# DC_MainBoard_Gh.net
KiCad netlist of a schematic drawn in EasyEDA Pro
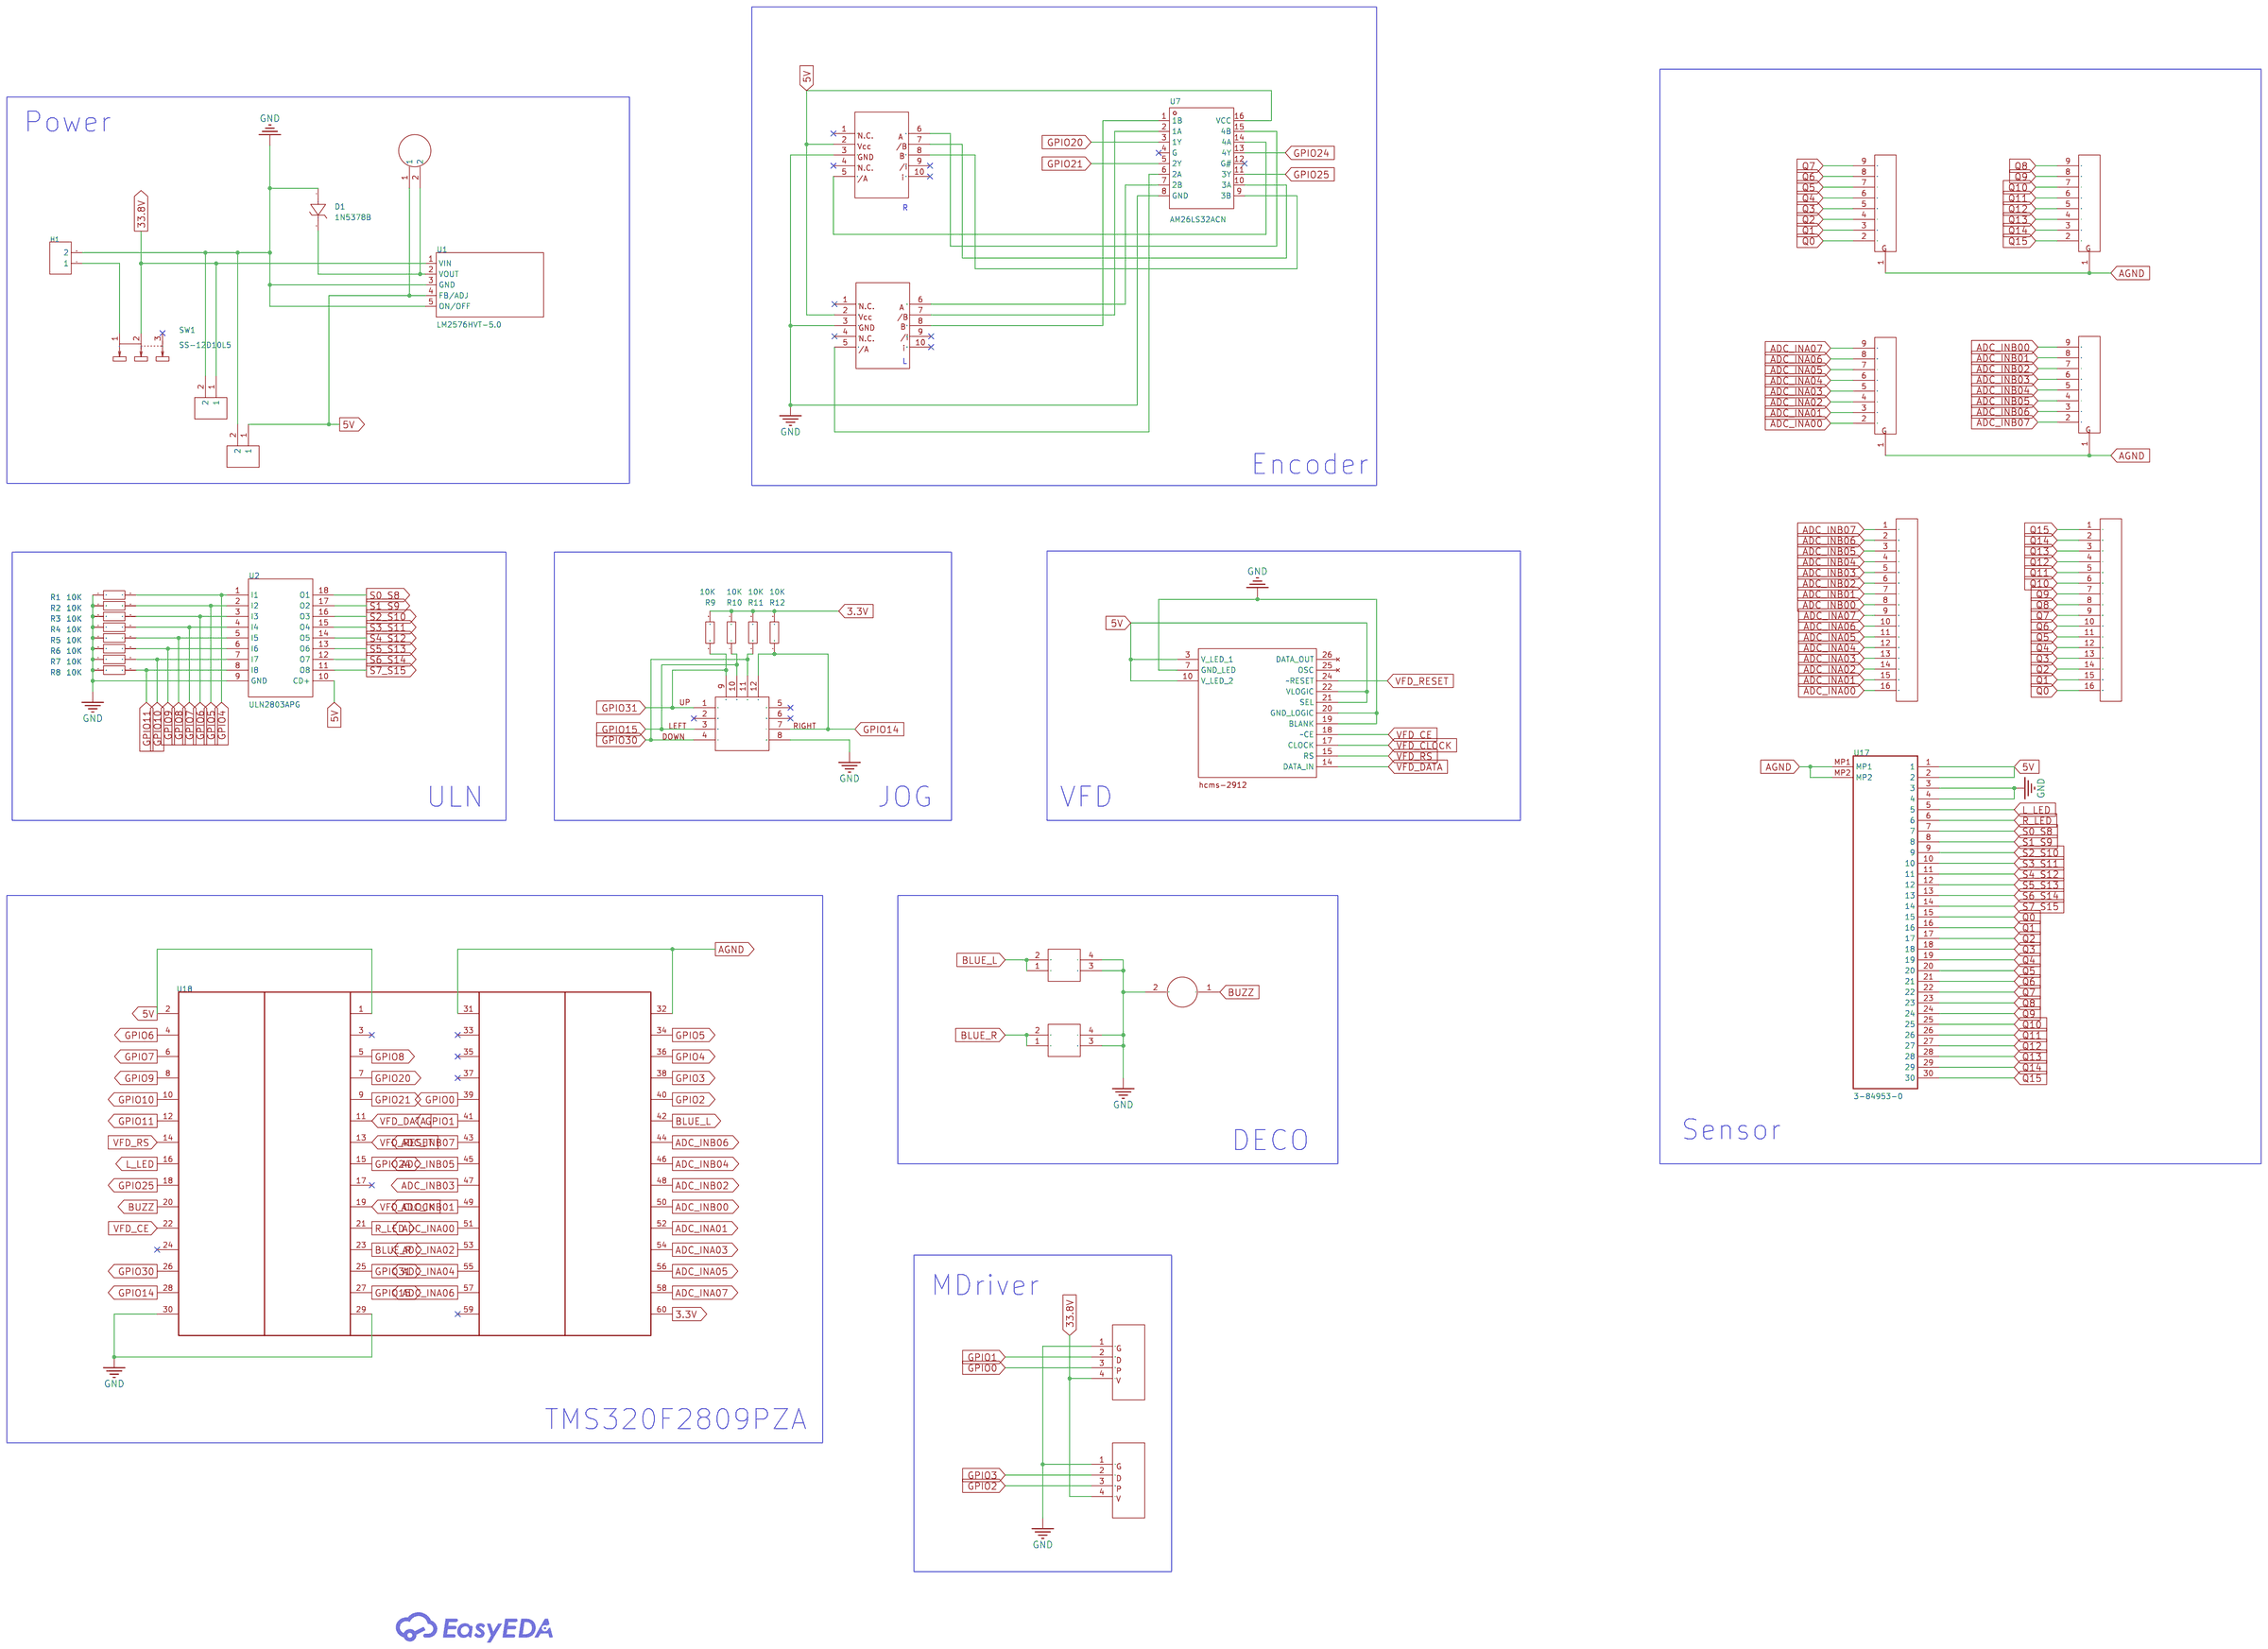
[diagram p0: schematic sheet]

(export (version "E")
  (design (tool "Eeschema 10.0.6"))
  (components
    (comp (ref "C1")
      (value "~")
      (footprint "easyedapro:100uF Capacitor")
      (libsource (lib "easyedapro") (part "100uF Capacitor"))
    )
    (comp (ref "C2")
      (value "~")
      (footprint "easyedapro:1000uF Capacitor")
      (libsource (lib "easyedapro") (part "1000uF Capacitor"))
    )
    (comp (ref "D1")
      (value "1N5378B")
      (footprint "easyedapro:DO-15_BD3.1-L6.7-P10.70-D0.9-FD")
      (fields (field (name "Manufacturer") "EIC"))
      (libsource (lib "easyedapro") (part "1N5378B"))
    )
    (comp (ref "H1")
      (value "~")
      (footprint "easyedapro:HDR-TH_2P-P2.54-V-F")
      (libsource (lib "easyedapro") (part "Header-Female-2.54_1x2"))
    )
    (comp (ref "L1")
      (value "~")
      (footprint "easyedapro:Indoctor")
      (libsource (lib "easyedapro") (part "Indoctor"))
    )
    (comp (ref "L2")
      (value "~")
      (footprint "easyedapro:NEMO_LED")
      (libsource (lib "easyedapro") (part "NEMO_LED"))
    )
    (comp (ref "L3")
      (value "~")
      (footprint "easyedapro:NEMO_LED")
      (libsource (lib "easyedapro") (part "NEMO_LED"))
    )
    (comp (ref "R1") (value "10K") (footprint "easyedapro:R0603") (libsource (lib "easyedapro") (part "Res")))
    (comp (ref "R2") (value "10K") (footprint "easyedapro:R0603") (libsource (lib "easyedapro") (part "Res")))
    (comp (ref "R3") (value "10K") (footprint "easyedapro:R0603") (libsource (lib "easyedapro") (part "Res")))
    (comp (ref "R4") (value "10K") (footprint "easyedapro:R0603") (libsource (lib "easyedapro") (part "Res")))
    (comp (ref "R5") (value "10K") (footprint "easyedapro:R0603") (libsource (lib "easyedapro") (part "Res")))
    (comp (ref "R6") (value "10K") (footprint "easyedapro:R0603") (libsource (lib "easyedapro") (part "Res")))
    (comp (ref "R7") (value "10K") (footprint "easyedapro:R0603") (libsource (lib "easyedapro") (part "Res")))
    (comp (ref "R8") (value "10K") (footprint "easyedapro:R0603") (libsource (lib "easyedapro") (part "Res")))
    (comp (ref "R9") (value "10K") (footprint "easyedapro:R0603") (libsource (lib "easyedapro") (part "Res")))
    (comp (ref "R10")
      (value "10K")
      (footprint "easyedapro:R0603")
      (libsource (lib "easyedapro") (part "Res"))
    )
    (comp (ref "R11")
      (value "10K")
      (footprint "easyedapro:R0603")
      (libsource (lib "easyedapro") (part "Res"))
    )
    (comp (ref "R12")
      (value "10K")
      (footprint "easyedapro:R0603")
      (libsource (lib "easyedapro") (part "Res"))
    )
    (comp (ref "SW1")
      (value "SS-12D10L5")
      (footprint "easyedapro:SW-TH_SS-12D10L5")
      (fields (field (name "Manufacturer") "XKB Connectivity(中国星坤)"))
      (libsource (lib "easyedapro") (part "SS-12D10L5"))
    )
    (comp (ref "U1")
      (value "LM2576HVT-5.0")
      (footprint "easyedapro:TO-220-5L_L10.2-W4.5-P1.71-L")
      (fields (field (name "Manufacturer") "HTC"))
      (libsource (lib "easyedapro") (part "LM2576HVT-5.0_C262789"))
    )
    (comp (ref "U2")
      (value "ULN2803APG")
      (footprint "easyedapro:DIP-18_L23.0-W6.5-P2.54-LS7.6-BL")
      (description "number of channels:Eight channels")
      (fields (field (name "Manufacturer") "TOSHIBA(东芝)"))
      (libsource (lib "easyedapro") (part "ULN2803APG"))
    )
    (comp (ref "U3")
      (value "~")
      (footprint "easyedapro:JOG_SW_DIP")
      (libsource (lib "easyedapro") (part "JOG_SW_DIP"))
    )
    (comp (ref "U4")
      (value "MDriver_L")
      (footprint "easyedapro:DC_Main_to_Motordriver_Connector_L")
      (libsource (lib "easyedapro") (part "DC_Main_to_Motordriver_Connector"))
    )
    (comp (ref "U5")
      (value "MDriver_R")
      (footprint "easyedapro:DC_Main_to_Motordriver_Connector_R")
      (libsource (lib "easyedapro") (part "DC_Main_to_Motordriver_Connector_R"))
    )
    (comp (ref "U6")
      (value "~")
      (footprint "easyedapro:BUZZER")
      (libsource (lib "easyedapro") (part "BUZZER"))
    )
    (comp (ref "U7")
      (value "AM26LS32ACN")
      (footprint "easyedapro:DIP-16_L20.0-W6.4-P2.54-LS7.6-BL")
      (fields (field (name "Manufacturer") "TI(德州仪器)"))
      (libsource (lib "easyedapro") (part "AM26LS32ACN"))
    )
    (comp (ref "U8")
      (value "~")
      (footprint "easyedapro:Encoder")
      (libsource (lib "easyedapro") (part "Encoder"))
    )
    (comp (ref "U9")
      (value "~")
      (footprint "easyedapro:Encoder")
      (libsource (lib "easyedapro") (part "Encoder"))
    )
    (comp (ref "U10") (value "~") (libsource (lib "easyedapro") (part "HCMS-2912")))
    (comp (ref "U11")
      (value "~")
      (footprint "easyedapro:Array")
      (libsource (lib "easyedapro") (part "Array"))
    )
    (comp (ref "U12")
      (value "~")
      (footprint "easyedapro:Array")
      (libsource (lib "easyedapro") (part "Array"))
    )
    (comp (ref "U13")
      (value "~")
      (footprint "easyedapro:Array")
      (libsource (lib "easyedapro") (part "Array"))
    )
    (comp (ref "U14")
      (value "~")
      (footprint "easyedapro:Array")
      (libsource (lib "easyedapro") (part "Array"))
    )
    (comp (ref "U15")
      (value "~")
      (footprint "easyedapro:C_Array")
      (libsource (lib "easyedapro") (part "C_Array"))
    )
    (comp (ref "U16")
      (value "~")
      (footprint "easyedapro:C_Array")
      (libsource (lib "easyedapro") (part "C_Array"))
    )
    (comp (ref "U17")
      (value "3-84953-0")
      (footprint "easyedapro:3849530")
      (libsource (lib "easyedapro") (part "3-84953-0"))
    )
    (comp (ref "U18") (value "~") (libsource (lib "easyedapro") (part "TMS320F2809PZA_DIP")))
  )
  (nets
    (net (code "1") (name "3.3V") (class "Default")
      (node (ref "R10") (pin "2") (pinfunction "2_2") (pintype "input"))
      (node (ref "R11") (pin "2") (pinfunction "2_2") (pintype "input"))
      (node (ref "R12") (pin "2") (pinfunction "2_2") (pintype "input"))
      (node (ref "R9") (pin "2") (pinfunction "2_2") (pintype "input"))
      (node (ref "U18") (pin "60") (pintype "unspecified"))
    )
    (net (code "2") (name "5V") (class "Default")
      (node (ref "C2") (pin "1") (pinfunction "1_1") (pintype "input"))
      (node (ref "L1") (pin "1") (pinfunction "1_1") (pintype "input"))
      (node (ref "U1") (pin "4") (pinfunction "FB/ADJ_4") (pintype "unspecified"))
      (node (ref "U10") (pin "10") (pinfunction "V_LED_2_10") (pintype "unspecified"))
      (node (ref "U10") (pin "21") (pinfunction "SEL_21") (pintype "unspecified"))
      (node (ref "U10") (pin "22") (pinfunction "VLOGIC_22") (pintype "unspecified"))
      (node (ref "U10") (pin "3") (pinfunction "V_LED_1_3") (pintype "unspecified"))
      (node (ref "U17") (pin "1") (pinfunction "1_1") (pintype "bidirectional"))
      (node (ref "U17") (pin "2") (pinfunction "2_2") (pintype "bidirectional"))
      (node (ref "U18") (pin "1") (pintype "unspecified"))
      (node (ref "U18") (pin "2") (pintype "unspecified"))
      (node (ref "U2") (pin "10") (pinfunction "CD+_10") (pintype "unspecified"))
      (node (ref "U7") (pin "16") (pinfunction "VCC_16") (pintype "unspecified"))
      (node (ref "U8") (pin "2") (pinfunction "2_2") (pintype "input"))
      (node (ref "U9") (pin "2") (pinfunction "2_2") (pintype "input"))
    )
    (net (code "3") (name "33.8V") (class "Default")
      (node (ref "C1") (pin "1") (pinfunction "1_1") (pintype "input"))
      (node (ref "SW1") (pin "2") (pinfunction "2_2") (pintype "unspecified"))
      (node (ref "U1") (pin "1") (pinfunction "VIN_1") (pintype "unspecified"))
      (node (ref "U4") (pin "4") (pinfunction "4_4") (pintype "input"))
      (node (ref "U5") (pin "4") (pinfunction "4_4") (pintype "input"))
    )
    (net (code "4") (name "ADC_INA00") (class "Default")
      (node (ref "U13") (pin "2") (pinfunction "2_2") (pintype "input"))
      (node (ref "U15") (pin "16") (pinfunction "16_16") (pintype "input"))
      (node (ref "U18") (pin "51") (pintype "unspecified"))
    )
    (net (code "5") (name "ADC_INA01") (class "Default")
      (node (ref "U13") (pin "3") (pinfunction "3_3") (pintype "input"))
      (node (ref "U15") (pin "15") (pinfunction "15_15") (pintype "input"))
      (node (ref "U18") (pin "52") (pintype "unspecified"))
    )
    (net (code "6") (name "ADC_INA02") (class "Default")
      (node (ref "U13") (pin "4") (pinfunction "4_4") (pintype "input"))
      (node (ref "U15") (pin "14") (pinfunction "14_14") (pintype "input"))
      (node (ref "U18") (pin "53") (pintype "unspecified"))
    )
    (net (code "7") (name "ADC_INA03") (class "Default")
      (node (ref "U13") (pin "5") (pinfunction "5_5") (pintype "input"))
      (node (ref "U15") (pin "13") (pinfunction "13_13") (pintype "input"))
      (node (ref "U18") (pin "54") (pintype "unspecified"))
    )
    (net (code "8") (name "ADC_INA04") (class "Default")
      (node (ref "U13") (pin "6") (pinfunction "6_6") (pintype "input"))
      (node (ref "U15") (pin "12") (pinfunction "12_12") (pintype "input"))
      (node (ref "U18") (pin "55") (pintype "unspecified"))
    )
    (net (code "9") (name "ADC_INA05") (class "Default")
      (node (ref "U13") (pin "7") (pinfunction "7_7") (pintype "input"))
      (node (ref "U15") (pin "11") (pinfunction "11_11") (pintype "input"))
      (node (ref "U18") (pin "56") (pintype "unspecified"))
    )
    (net (code "10") (name "ADC_INA06") (class "Default")
      (node (ref "U13") (pin "8") (pinfunction "8_8") (pintype "input"))
      (node (ref "U15") (pin "10") (pinfunction "10_10") (pintype "input"))
      (node (ref "U18") (pin "57") (pintype "unspecified"))
    )
    (net (code "11") (name "ADC_INA07") (class "Default")
      (node (ref "U13") (pin "9") (pinfunction "9_9") (pintype "input"))
      (node (ref "U15") (pin "9") (pinfunction "9_9") (pintype "input"))
      (node (ref "U18") (pin "58") (pintype "unspecified"))
    )
    (net (code "12") (name "ADC_INB00") (class "Default")
      (node (ref "U14") (pin "9") (pinfunction "9_9") (pintype "input"))
      (node (ref "U15") (pin "8") (pinfunction "8_8") (pintype "input"))
      (node (ref "U18") (pin "50") (pintype "unspecified"))
    )
    (net (code "13") (name "ADC_INB01") (class "Default")
      (node (ref "U14") (pin "8") (pinfunction "8_8") (pintype "input"))
      (node (ref "U15") (pin "7") (pinfunction "7_7") (pintype "input"))
      (node (ref "U18") (pin "49") (pintype "unspecified"))
    )
    (net (code "14") (name "ADC_INB02") (class "Default")
      (node (ref "U14") (pin "7") (pinfunction "7_7") (pintype "input"))
      (node (ref "U15") (pin "6") (pinfunction "6_6") (pintype "input"))
      (node (ref "U18") (pin "48") (pintype "unspecified"))
    )
    (net (code "15") (name "ADC_INB03") (class "Default")
      (node (ref "U14") (pin "6") (pinfunction "6_6") (pintype "input"))
      (node (ref "U15") (pin "5") (pinfunction "5_5") (pintype "input"))
      (node (ref "U18") (pin "47") (pintype "unspecified"))
    )
    (net (code "16") (name "ADC_INB04") (class "Default")
      (node (ref "U14") (pin "5") (pinfunction "5_5") (pintype "input"))
      (node (ref "U15") (pin "4") (pinfunction "4_4") (pintype "input"))
      (node (ref "U18") (pin "46") (pintype "unspecified"))
    )
    (net (code "17") (name "ADC_INB05") (class "Default")
      (node (ref "U14") (pin "4") (pinfunction "4_4") (pintype "input"))
      (node (ref "U15") (pin "3") (pinfunction "3_3") (pintype "input"))
      (node (ref "U18") (pin "45") (pintype "unspecified"))
    )
    (net (code "18") (name "ADC_INB06") (class "Default")
      (node (ref "U14") (pin "3") (pinfunction "3_3") (pintype "input"))
      (node (ref "U15") (pin "2") (pinfunction "2_2") (pintype "input"))
      (node (ref "U18") (pin "44") (pintype "unspecified"))
    )
    (net (code "19") (name "ADC_INB07") (class "Default")
      (node (ref "U14") (pin "2") (pinfunction "2_2") (pintype "input"))
      (node (ref "U15") (pin "1") (pinfunction "1_1") (pintype "input"))
      (node (ref "U18") (pin "43") (pintype "unspecified"))
    )
    (net (code "20") (name "AGND") (class "Default")
      (node (ref "U11") (pin "1") (pinfunction "1_1") (pintype "input"))
      (node (ref "U12") (pin "1") (pinfunction "1_1") (pintype "input"))
      (node (ref "U13") (pin "1") (pinfunction "1_1") (pintype "input"))
      (node (ref "U14") (pin "1") (pinfunction "1_1") (pintype "input"))
      (node (ref "U17") (pin "MP1") (pinfunction "MP1_MP1") (pintype "bidirectional"))
      (node (ref "U17") (pin "MP2") (pinfunction "MP2_MP2") (pintype "bidirectional"))
      (node (ref "U18") (pin "31") (pintype "unspecified"))
      (node (ref "U18") (pin "32") (pintype "unspecified"))
    )
    (net (code "21") (name "BLUE_L") (class "Default")
      (node (ref "L2") (pin "1") (pinfunction "1_1") (pintype "input"))
      (node (ref "L2") (pin "2") (pinfunction "2_2") (pintype "input"))
      (node (ref "U18") (pin "42") (pintype "unspecified"))
    )
    (net (code "22") (name "BLUE_R") (class "Default")
      (node (ref "L3") (pin "1") (pinfunction "1_1") (pintype "input"))
      (node (ref "L3") (pin "2") (pinfunction "2_2") (pintype "input"))
      (node (ref "U18") (pin "23") (pintype "unspecified"))
    )
    (net (code "23") (name "BUZZ") (class "Default")
      (node (ref "U18") (pin "20") (pintype "unspecified"))
      (node (ref "U6") (pin "1") (pinfunction "1_1") (pintype "input"))
    )
    (net (code "24") (name "GND") (class "Default")
      (node (ref "C1") (pin "2") (pinfunction "2_2") (pintype "input"))
      (node (ref "C2") (pin "2") (pinfunction "2_2") (pintype "input"))
      (node (ref "D1") (pin "1") (pinfunction "+_1") (pintype "unspecified"))
      (node (ref "H1") (pin "2") (pinfunction "2_2") (pintype "input"))
      (node (ref "L2") (pin "3") (pinfunction "3_3") (pintype "input"))
      (node (ref "L2") (pin "4") (pinfunction "4_4") (pintype "input"))
      (node (ref "L3") (pin "3") (pinfunction "3_3") (pintype "input"))
      (node (ref "L3") (pin "4") (pinfunction "4_4") (pintype "input"))
      (node (ref "R1") (pin "1") (pinfunction "1_1") (pintype "input"))
      (node (ref "R2") (pin "1") (pinfunction "1_1") (pintype "input"))
      (node (ref "R3") (pin "1") (pinfunction "1_1") (pintype "input"))
      (node (ref "R4") (pin "1") (pinfunction "1_1") (pintype "input"))
      (node (ref "R5") (pin "1") (pinfunction "1_1") (pintype "input"))
      (node (ref "R6") (pin "1") (pinfunction "1_1") (pintype "input"))
      (node (ref "R7") (pin "1") (pinfunction "1_1") (pintype "input"))
      (node (ref "R8") (pin "1") (pinfunction "1_1") (pintype "input"))
      (node (ref "U1") (pin "3") (pinfunction "GND_3") (pintype "unspecified"))
      (node (ref "U1") (pin "5") (pinfunction "ON/OFF_5") (pintype "unspecified"))
      (node (ref "U10") (pin "19") (pinfunction "BLANK_19") (pintype "unspecified"))
      (node (ref "U10") (pin "20") (pinfunction "GND_LOGIC_20") (pintype "unspecified"))
      (node (ref "U10") (pin "7") (pinfunction "GND_LED_7") (pintype "unspecified"))
      (node (ref "U17") (pin "3") (pinfunction "3_3") (pintype "bidirectional"))
      (node (ref "U17") (pin "4") (pinfunction "4_4") (pintype "bidirectional"))
      (node (ref "U18") (pin "29") (pintype "unspecified"))
      (node (ref "U18") (pin "30") (pintype "unspecified"))
      (node (ref "U2") (pin "9") (pinfunction "GND_9") (pintype "unspecified"))
      (node (ref "U3") (pin "8") (pinfunction "8_8") (pintype "input"))
      (node (ref "U4") (pin "1") (pinfunction "1_1") (pintype "input"))
      (node (ref "U5") (pin "1") (pinfunction "1_1") (pintype "input"))
      (node (ref "U6") (pin "2") (pinfunction "2_2") (pintype "input"))
      (node (ref "U7") (pin "8") (pinfunction "GND_8") (pintype "unspecified"))
      (node (ref "U8") (pin "3") (pinfunction "3_3") (pintype "input"))
      (node (ref "U9") (pin "3") (pinfunction "3_3") (pintype "input"))
    )
    (net (code "25") (name "GPIO0") (class "Default")
      (node (ref "U18") (pin "39") (pintype "unspecified"))
      (node (ref "U4") (pin "3") (pinfunction "3_3") (pintype "input"))
    )
    (net (code "26") (name "GPIO1") (class "Default")
      (node (ref "U18") (pin "41") (pintype "unspecified"))
      (node (ref "U4") (pin "2") (pinfunction "2_2") (pintype "input"))
    )
    (net (code "27") (name "GPIO2") (class "Default")
      (node (ref "U18") (pin "40") (pintype "unspecified"))
      (node (ref "U5") (pin "3") (pinfunction "3_3") (pintype "input"))
    )
    (net (code "28") (name "GPIO3") (class "Default")
      (node (ref "U18") (pin "38") (pintype "unspecified"))
      (node (ref "U5") (pin "2") (pinfunction "2_2") (pintype "input"))
    )
    (net (code "29") (name "GPIO4") (class "Default")
      (node (ref "R1") (pin "2") (pinfunction "2_2") (pintype "input"))
      (node (ref "U18") (pin "36") (pintype "unspecified"))
      (node (ref "U2") (pin "1") (pinfunction "I1_1") (pintype "input"))
    )
    (net (code "30") (name "GPIO5") (class "Default")
      (node (ref "R2") (pin "2") (pinfunction "2_2") (pintype "input"))
      (node (ref "U18") (pin "34") (pintype "unspecified"))
      (node (ref "U2") (pin "2") (pinfunction "I2_2") (pintype "input"))
    )
    (net (code "31") (name "GPIO6") (class "Default")
      (node (ref "R3") (pin "2") (pinfunction "2_2") (pintype "input"))
      (node (ref "U18") (pin "4") (pintype "unspecified"))
      (node (ref "U2") (pin "3") (pinfunction "I3_3") (pintype "input"))
    )
    (net (code "32") (name "GPIO7") (class "Default")
      (node (ref "R4") (pin "2") (pinfunction "2_2") (pintype "input"))
      (node (ref "U18") (pin "6") (pintype "unspecified"))
      (node (ref "U2") (pin "4") (pinfunction "I4_4") (pintype "input"))
    )
    (net (code "33") (name "GPIO8") (class "Default")
      (node (ref "R5") (pin "2") (pinfunction "2_2") (pintype "input"))
      (node (ref "U18") (pin "5") (pintype "unspecified"))
      (node (ref "U2") (pin "5") (pinfunction "I5_5") (pintype "input"))
    )
    (net (code "34") (name "GPIO9") (class "Default")
      (node (ref "R6") (pin "2") (pinfunction "2_2") (pintype "input"))
      (node (ref "U18") (pin "8") (pintype "unspecified"))
      (node (ref "U2") (pin "6") (pinfunction "I6_6") (pintype "input"))
    )
    (net (code "35") (name "GPIO10") (class "Default")
      (node (ref "R7") (pin "2") (pinfunction "2_2") (pintype "input"))
      (node (ref "U18") (pin "10") (pintype "unspecified"))
      (node (ref "U2") (pin "7") (pinfunction "I7_7") (pintype "input"))
    )
    (net (code "36") (name "GPIO11") (class "Default")
      (node (ref "R8") (pin "2") (pinfunction "2_2") (pintype "input"))
      (node (ref "U18") (pin "12") (pintype "unspecified"))
      (node (ref "U2") (pin "8") (pinfunction "I8_8") (pintype "input"))
    )
    (net (code "37") (name "GPIO14") (class "Default")
      (node (ref "R12") (pin "1") (pinfunction "1_1") (pintype "input"))
      (node (ref "U18") (pin "28") (pintype "unspecified"))
      (node (ref "U3") (pin "12") (pinfunction "12_12") (pintype "input"))
      (node (ref "U3") (pin "7") (pinfunction "7_7") (pintype "input"))
    )
    (net (code "38") (name "GPIO15") (class "Default")
      (node (ref "R10") (pin "1") (pinfunction "1_1") (pintype "input"))
      (node (ref "U18") (pin "27") (pintype "unspecified"))
      (node (ref "U3") (pin "10") (pinfunction "10_10") (pintype "input"))
      (node (ref "U3") (pin "3") (pinfunction "3_3") (pintype "input"))
    )
    (net (code "39") (name "GPIO20") (class "Default")
      (node (ref "U18") (pin "7") (pintype "unspecified"))
      (node (ref "U7") (pin "3") (pinfunction "1Y_3") (pintype "unspecified"))
    )
    (net (code "40") (name "GPIO21") (class "Default")
      (node (ref "U18") (pin "9") (pintype "unspecified"))
      (node (ref "U7") (pin "5") (pinfunction "2Y_5") (pintype "unspecified"))
    )
    (net (code "41") (name "GPIO24") (class "Default")
      (node (ref "U18") (pin "15") (pintype "unspecified"))
      (node (ref "U7") (pin "13") (pinfunction "4Y_13") (pintype "unspecified"))
    )
    (net (code "42") (name "GPIO25") (class "Default")
      (node (ref "U18") (pin "18") (pintype "unspecified"))
      (node (ref "U7") (pin "11") (pinfunction "3Y_11") (pintype "unspecified"))
    )
    (net (code "43") (name "GPIO30") (class "Default")
      (node (ref "R11") (pin "1") (pinfunction "1_1") (pintype "input"))
      (node (ref "U18") (pin "26") (pintype "unspecified"))
      (node (ref "U3") (pin "11") (pinfunction "11_11") (pintype "input"))
      (node (ref "U3") (pin "4") (pinfunction "4_4") (pintype "input"))
    )
    (net (code "44") (name "GPIO31") (class "Default")
      (node (ref "R9") (pin "1") (pinfunction "1_1") (pintype "input"))
      (node (ref "U18") (pin "25") (pintype "unspecified"))
      (node (ref "U3") (pin "1") (pinfunction "1_1") (pintype "input"))
      (node (ref "U3") (pin "9") (pinfunction "9_9") (pintype "input"))
    )
    (net (code "45") (name "L_LED") (class "Default")
      (node (ref "U17") (pin "5") (pinfunction "5_5") (pintype "bidirectional"))
      (node (ref "U18") (pin "16") (pintype "unspecified"))
    )
    (net (code "46") (name "Net-(D1--)") (class "Default")
      (node (ref "D1") (pin "2") (pinfunction "-_2") (pintype "unspecified"))
      (node (ref "L1") (pin "2") (pinfunction "2_2") (pintype "input"))
      (node (ref "U1") (pin "2") (pinfunction "VOUT_2") (pintype "unspecified"))
    )
    (net (code "47") (name "Net-(H1-Pad1)") (class "Default")
      (node (ref "H1") (pin "1") (pinfunction "1_1") (pintype "input"))
      (node (ref "SW1") (pin "1") (pinfunction "1_1") (pintype "unspecified"))
    )
    (net (code "48") (name "Net-(U7-1A)") (class "Default")
      (node (ref "U7") (pin "2") (pinfunction "1A_2") (pintype "unspecified"))
      (node (ref "U8") (pin "7") (pinfunction "7_7") (pintype "input"))
    )
    (net (code "49") (name "Net-(U7-1B)") (class "Default")
      (node (ref "U7") (pin "1") (pinfunction "1B_1") (pintype "unspecified"))
      (node (ref "U8") (pin "8") (pinfunction "8_8") (pintype "input"))
    )
    (net (code "50") (name "Net-(U7-2A)") (class "Default")
      (node (ref "U7") (pin "6") (pinfunction "2A_6") (pintype "unspecified"))
      (node (ref "U8") (pin "5") (pinfunction "5_5") (pintype "input"))
    )
    (net (code "51") (name "Net-(U7-2B)") (class "Default")
      (node (ref "U7") (pin "7") (pinfunction "2B_7") (pintype "unspecified"))
      (node (ref "U8") (pin "6") (pinfunction "6_6") (pintype "input"))
    )
    (net (code "52") (name "Net-(U7-3A)") (class "Default")
      (node (ref "U7") (pin "10") (pinfunction "3A_10") (pintype "unspecified"))
      (node (ref "U9") (pin "7") (pinfunction "7_7") (pintype "input"))
    )
    (net (code "53") (name "Net-(U7-3B)") (class "Default")
      (node (ref "U7") (pin "9") (pinfunction "3B_9") (pintype "unspecified"))
      (node (ref "U9") (pin "8") (pinfunction "8_8") (pintype "input"))
    )
    (net (code "54") (name "Net-(U7-4A)") (class "Default")
      (node (ref "U7") (pin "14") (pinfunction "4A_14") (pintype "unspecified"))
      (node (ref "U9") (pin "5") (pinfunction "5_5") (pintype "input"))
    )
    (net (code "55") (name "Net-(U7-4B)") (class "Default")
      (node (ref "U7") (pin "15") (pinfunction "4B_15") (pintype "unspecified"))
      (node (ref "U9") (pin "6") (pinfunction "6_6") (pintype "input"))
    )
    (net (code "56") (name "Q0") (class "Default")
      (node (ref "U11") (pin "2") (pinfunction "2_2") (pintype "input"))
      (node (ref "U16") (pin "16") (pinfunction "16_16") (pintype "input"))
      (node (ref "U17") (pin "15") (pinfunction "15_15") (pintype "bidirectional"))
    )
    (net (code "57") (name "Q1") (class "Default")
      (node (ref "U11") (pin "3") (pinfunction "3_3") (pintype "input"))
      (node (ref "U16") (pin "15") (pinfunction "15_15") (pintype "input"))
      (node (ref "U17") (pin "16") (pinfunction "16_16") (pintype "bidirectional"))
    )
    (net (code "58") (name "Q2") (class "Default")
      (node (ref "U11") (pin "4") (pinfunction "4_4") (pintype "input"))
      (node (ref "U16") (pin "14") (pinfunction "14_14") (pintype "input"))
      (node (ref "U17") (pin "17") (pinfunction "17_17") (pintype "bidirectional"))
    )
    (net (code "59") (name "Q3") (class "Default")
      (node (ref "U11") (pin "5") (pinfunction "5_5") (pintype "input"))
      (node (ref "U16") (pin "13") (pinfunction "13_13") (pintype "input"))
      (node (ref "U17") (pin "18") (pinfunction "18_18") (pintype "bidirectional"))
    )
    (net (code "60") (name "Q4") (class "Default")
      (node (ref "U11") (pin "6") (pinfunction "6_6") (pintype "input"))
      (node (ref "U16") (pin "12") (pinfunction "12_12") (pintype "input"))
      (node (ref "U17") (pin "19") (pinfunction "19_19") (pintype "bidirectional"))
    )
    (net (code "61") (name "Q5") (class "Default")
      (node (ref "U11") (pin "7") (pinfunction "7_7") (pintype "input"))
      (node (ref "U16") (pin "11") (pinfunction "11_11") (pintype "input"))
      (node (ref "U17") (pin "20") (pinfunction "20_20") (pintype "bidirectional"))
    )
    (net (code "62") (name "Q6") (class "Default")
      (node (ref "U11") (pin "8") (pinfunction "8_8") (pintype "input"))
      (node (ref "U16") (pin "10") (pinfunction "10_10") (pintype "input"))
      (node (ref "U17") (pin "21") (pinfunction "21_21") (pintype "bidirectional"))
    )
    (net (code "63") (name "Q7") (class "Default")
      (node (ref "U11") (pin "9") (pinfunction "9_9") (pintype "input"))
      (node (ref "U16") (pin "9") (pinfunction "9_9") (pintype "input"))
      (node (ref "U17") (pin "22") (pinfunction "22_22") (pintype "bidirectional"))
    )
    (net (code "64") (name "Q8") (class "Default")
      (node (ref "U12") (pin "9") (pinfunction "9_9") (pintype "input"))
      (node (ref "U16") (pin "8") (pinfunction "8_8") (pintype "input"))
      (node (ref "U17") (pin "23") (pinfunction "23_23") (pintype "bidirectional"))
    )
    (net (code "65") (name "Q9") (class "Default")
      (node (ref "U12") (pin "8") (pinfunction "8_8") (pintype "input"))
      (node (ref "U16") (pin "7") (pinfunction "7_7") (pintype "input"))
      (node (ref "U17") (pin "24") (pinfunction "24_24") (pintype "bidirectional"))
    )
    (net (code "66") (name "Q10") (class "Default")
      (node (ref "U12") (pin "7") (pinfunction "7_7") (pintype "input"))
      (node (ref "U16") (pin "6") (pinfunction "6_6") (pintype "input"))
      (node (ref "U17") (pin "25") (pinfunction "25_25") (pintype "bidirectional"))
    )
    (net (code "67") (name "Q11") (class "Default")
      (node (ref "U12") (pin "6") (pinfunction "6_6") (pintype "input"))
      (node (ref "U16") (pin "5") (pinfunction "5_5") (pintype "input"))
      (node (ref "U17") (pin "26") (pinfunction "26_26") (pintype "bidirectional"))
    )
    (net (code "68") (name "Q12") (class "Default")
      (node (ref "U12") (pin "5") (pinfunction "5_5") (pintype "input"))
      (node (ref "U16") (pin "4") (pinfunction "4_4") (pintype "input"))
      (node (ref "U17") (pin "27") (pinfunction "27_27") (pintype "bidirectional"))
    )
    (net (code "69") (name "Q13") (class "Default")
      (node (ref "U12") (pin "4") (pinfunction "4_4") (pintype "input"))
      (node (ref "U16") (pin "3") (pinfunction "3_3") (pintype "input"))
      (node (ref "U17") (pin "28") (pinfunction "28_28") (pintype "bidirectional"))
    )
    (net (code "70") (name "Q14") (class "Default")
      (node (ref "U12") (pin "3") (pinfunction "3_3") (pintype "input"))
      (node (ref "U16") (pin "2") (pinfunction "2_2") (pintype "input"))
      (node (ref "U17") (pin "29") (pinfunction "29_29") (pintype "bidirectional"))
    )
    (net (code "71") (name "Q15") (class "Default")
      (node (ref "U12") (pin "2") (pinfunction "2_2") (pintype "input"))
      (node (ref "U16") (pin "1") (pinfunction "1_1") (pintype "input"))
      (node (ref "U17") (pin "30") (pinfunction "30_30") (pintype "bidirectional"))
    )
    (net (code "72") (name "R_LED") (class "Default")
      (node (ref "U17") (pin "6") (pinfunction "6_6") (pintype "bidirectional"))
      (node (ref "U18") (pin "21") (pintype "unspecified"))
    )
    (net (code "73") (name "S0_S8") (class "Default")
      (node (ref "U17") (pin "7") (pinfunction "7_7") (pintype "bidirectional"))
      (node (ref "U2") (pin "18") (pinfunction "O1_18") (pintype "unspecified"))
    )
    (net (code "74") (name "S1_S9") (class "Default")
      (node (ref "U17") (pin "8") (pinfunction "8_8") (pintype "bidirectional"))
      (node (ref "U2") (pin "17") (pinfunction "O2_17") (pintype "unspecified"))
    )
    (net (code "75") (name "S2_S10") (class "Default")
      (node (ref "U17") (pin "9") (pinfunction "9_9") (pintype "bidirectional"))
      (node (ref "U2") (pin "16") (pinfunction "O3_16") (pintype "unspecified"))
    )
    (net (code "76") (name "S3_S11") (class "Default")
      (node (ref "U17") (pin "10") (pinfunction "10_10") (pintype "bidirectional"))
      (node (ref "U2") (pin "15") (pinfunction "O4_15") (pintype "unspecified"))
    )
    (net (code "77") (name "S4_S12") (class "Default")
      (node (ref "U17") (pin "11") (pinfunction "11_11") (pintype "bidirectional"))
      (node (ref "U2") (pin "14") (pinfunction "O5_14") (pintype "unspecified"))
    )
    (net (code "78") (name "S5_S13") (class "Default")
      (node (ref "U17") (pin "12") (pinfunction "12_12") (pintype "bidirectional"))
      (node (ref "U2") (pin "13") (pinfunction "O6_13") (pintype "unspecified"))
    )
    (net (code "79") (name "S6_S14") (class "Default")
      (node (ref "U17") (pin "13") (pinfunction "13_13") (pintype "bidirectional"))
      (node (ref "U2") (pin "12") (pinfunction "O7_12") (pintype "unspecified"))
    )
    (net (code "80") (name "S7_S15") (class "Default")
      (node (ref "U17") (pin "14") (pinfunction "14_14") (pintype "bidirectional"))
      (node (ref "U2") (pin "11") (pinfunction "O8_11") (pintype "unspecified"))
    )
    (net (code "81") (name "VFD_CE") (class "Default")
      (node (ref "U10") (pin "18") (pinfunction "~CE_18") (pintype "unspecified"))
      (node (ref "U18") (pin "22") (pintype "unspecified"))
    )
    (net (code "82") (name "VFD_CLOCK") (class "Default")
      (node (ref "U10") (pin "17") (pinfunction "CLOCK_17") (pintype "unspecified"))
      (node (ref "U18") (pin "19") (pintype "unspecified"))
    )
    (net (code "83") (name "VFD_DATA") (class "Default")
      (node (ref "U10") (pin "14") (pinfunction "DATA_IN_14") (pintype "unspecified"))
      (node (ref "U18") (pin "11") (pintype "unspecified"))
    )
    (net (code "84") (name "VFD_RESET") (class "Default")
      (node (ref "U10") (pin "24") (pinfunction "~RESET_24") (pintype "unspecified"))
      (node (ref "U18") (pin "13") (pintype "unspecified"))
    )
    (net (code "85") (name "VFD_RS") (class "Default")
      (node (ref "U10") (pin "15") (pinfunction "RS_15") (pintype "unspecified"))
      (node (ref "U18") (pin "14") (pintype "unspecified"))
    )
    (net (code "86") (name "unconnected-(SW1-Pad3)") (class "Default")
      (node (ref "SW1") (pin "3") (pinfunction "3_3") (pintype "unspecified+no_connect"))
    )
    (net (code "87") (name "unconnected-(U3-Pad2)") (class "Default")
      (node (ref "U3") (pin "2") (pinfunction "2_2") (pintype "input+no_connect"))
    )
    (net (code "88") (name "unconnected-(U3-Pad5)") (class "Default")
      (node (ref "U3") (pin "5") (pinfunction "5_5") (pintype "input+no_connect"))
    )
    (net (code "89") (name "unconnected-(U3-Pad6)") (class "Default")
      (node (ref "U3") (pin "6") (pinfunction "6_6") (pintype "input+no_connect"))
    )
    (net (code "90") (name "unconnected-(U7-G#-Pad12)") (class "Default")
      (node (ref "U7") (pin "12") (pinfunction "G#_12") (pintype "unspecified+no_connect"))
    )
    (net (code "91") (name "unconnected-(U7-G-Pad4)") (class "Default")
      (node (ref "U7") (pin "4") (pinfunction "G_4") (pintype "unspecified+no_connect"))
    )
    (net (code "92") (name "unconnected-(U8-Pad1)") (class "Default")
      (node (ref "U8") (pin "1") (pinfunction "1_1") (pintype "input+no_connect"))
    )
    (net (code "93") (name "unconnected-(U8-Pad4)") (class "Default")
      (node (ref "U8") (pin "4") (pinfunction "4_4") (pintype "input+no_connect"))
    )
    (net (code "94") (name "unconnected-(U8-Pad9)") (class "Default")
      (node (ref "U8") (pin "9") (pinfunction "9_9") (pintype "input+no_connect"))
    )
    (net (code "95") (name "unconnected-(U8-Pad10)") (class "Default")
      (node (ref "U8") (pin "10") (pinfunction "10_10") (pintype "input+no_connect"))
    )
    (net (code "96") (name "unconnected-(U9-Pad1)") (class "Default")
      (node (ref "U9") (pin "1") (pinfunction "1_1") (pintype "input+no_connect"))
    )
    (net (code "97") (name "unconnected-(U9-Pad4)") (class "Default")
      (node (ref "U9") (pin "4") (pinfunction "4_4") (pintype "input+no_connect"))
    )
    (net (code "98") (name "unconnected-(U9-Pad9)") (class "Default")
      (node (ref "U9") (pin "9") (pinfunction "9_9") (pintype "input+no_connect"))
    )
    (net (code "99") (name "unconnected-(U9-Pad10)") (class "Default")
      (node (ref "U9") (pin "10") (pinfunction "10_10") (pintype "input+no_connect"))
    )
    (net (code "100") (name "unconnected-(U10-DATA_OUT-Pad26)") (class "Default")
      (node (ref "U10") (pin "26") (pinfunction "DATA_OUT_26") (pintype "no_connect"))
    )
    (net (code "101") (name "unconnected-(U10-OSC-Pad25)") (class "Default")
      (node (ref "U10") (pin "25") (pinfunction "OSC_25") (pintype "no_connect"))
    )
    (net (code "102") (name "unconnected-(U18-Pad3)") (class "Default")
      (node (ref "U18") (pin "3") (pintype "unspecified+no_connect"))
    )
    (net (code "103") (name "unconnected-(U18-Pad17)") (class "Default")
      (node (ref "U18") (pin "17") (pintype "unspecified+no_connect"))
    )
    (net (code "104") (name "unconnected-(U18-Pad24)") (class "Default")
      (node (ref "U18") (pin "24") (pintype "unspecified+no_connect"))
    )
    (net (code "105") (name "unconnected-(U18-Pad33)") (class "Default")
      (node (ref "U18") (pin "33") (pintype "unspecified+no_connect"))
    )
    (net (code "106") (name "unconnected-(U18-Pad35)") (class "Default")
      (node (ref "U18") (pin "35") (pintype "unspecified+no_connect"))
    )
    (net (code "107") (name "unconnected-(U18-Pad37)") (class "Default")
      (node (ref "U18") (pin "37") (pintype "unspecified+no_connect"))
    )
    (net (code "108") (name "unconnected-(U18-Pad59)") (class "Default")
      (node (ref "U18") (pin "59") (pintype "unspecified+no_connect"))
    )
  )
)
